# Peripheral.net
KiCad netlist of a schematic drawn in Altium Designer
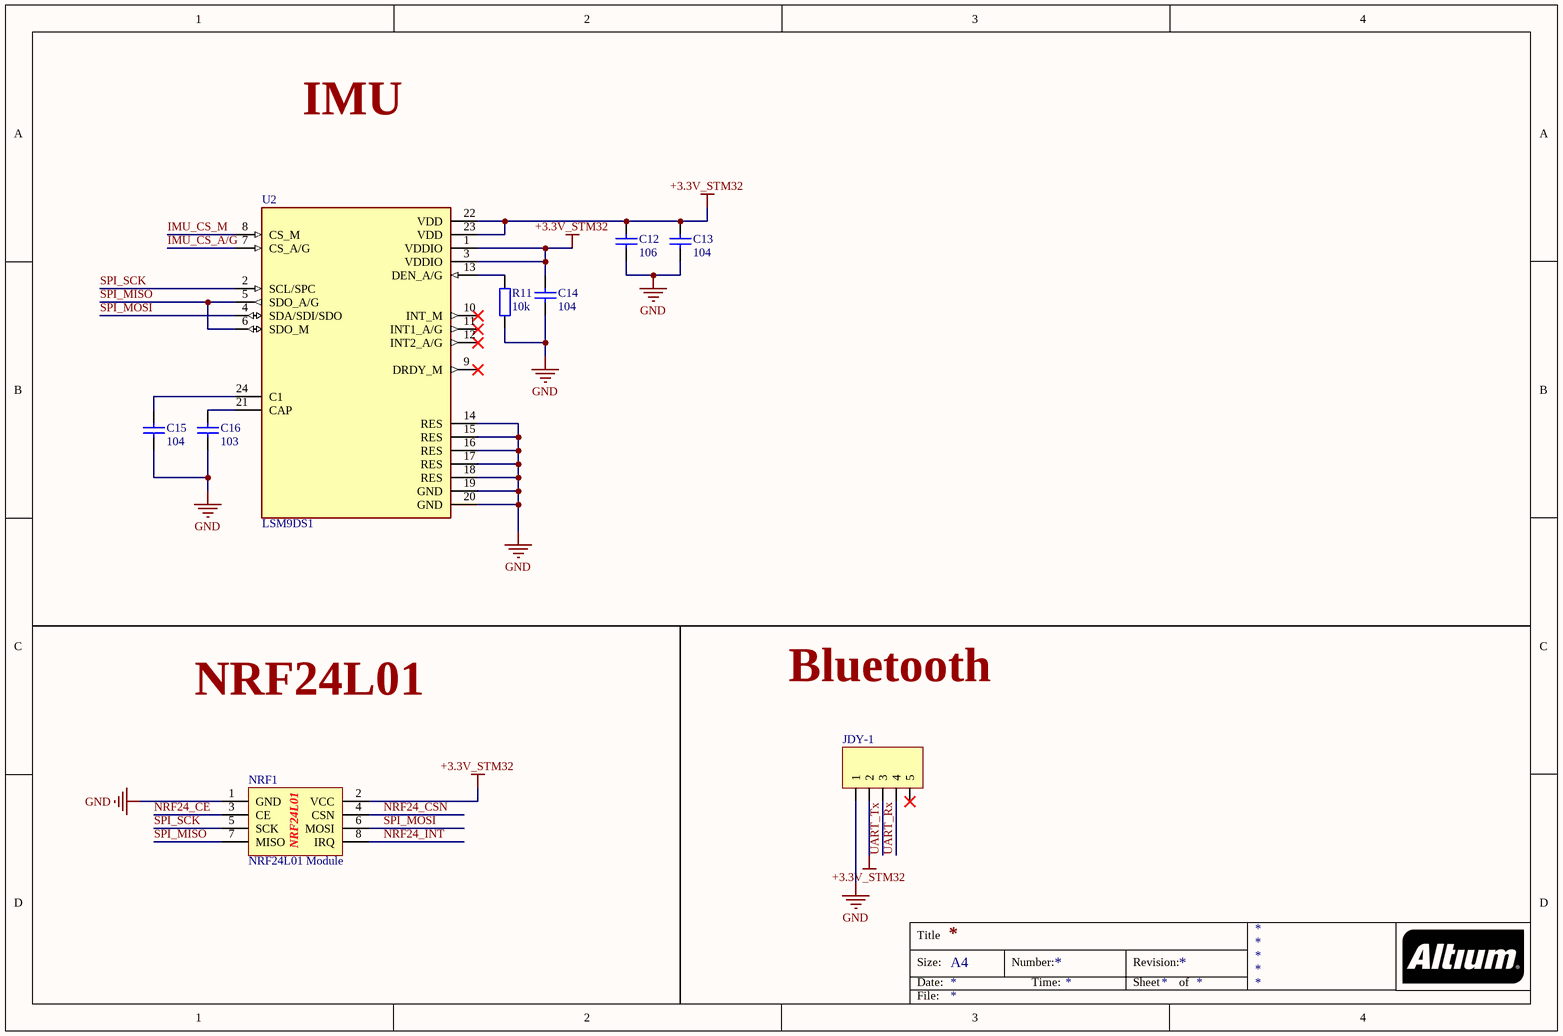
[diagram p0: Peripheral.SchDoc]

(export (version "E")
  (design (tool "Eeschema 10.0.6"))
  (components
    (comp (ref "C12")
      (value "106")
      (footprint "tu 0603")
      (description "Dán")
      (libsource (lib "Altium_Lib_by_KhueNguyenCreator") (part "Tu 0603 106 16V 20%"))
    )
    (comp (ref "C13")
      (value "104")
      (footprint "tu 0603")
      (description "Dán")
      (libsource (lib "Altium_Lib_by_KhueNguyenCreator") (part "Tu 0603 104 50V 10%"))
    )
    (comp (ref "C14")
      (value "104")
      (footprint "tu 0603")
      (description "Dán")
      (libsource (lib "Altium_Lib_by_KhueNguyenCreator") (part "Tu 0603 104 50V 10%"))
    )
    (comp (ref "C15")
      (value "104")
      (footprint "tu 0603")
      (description "Dán")
      (libsource (lib "Altium_Lib_by_KhueNguyenCreator") (part "Tu 0603 104 50V 10%"))
    )
    (comp (ref "C16")
      (value "103")
      (footprint "tu 0603")
      (description "Dán")
      (libsource (lib "Altium_Lib_by_KhueNguyenCreator") (part "Tu 0603 103 50V 10%"))
    )
    (comp (ref "JDY-1")
      (value "JP 1x5 2.54")
      (footprint "JP 1x5 CC")
      (description "Cắm")
      (libsource (lib "Altium_Lib_by_KhueNguyenCreator") (part "JP 1x5 2.54 Cai Cong"))
    )
    (comp (ref "NRF1")
      (value "NRF24L01 Module")
      (footprint "NRF24L01")
      (libsource (lib "Altium_Lib_by_KhueNguyenCreator") (part "NRF24L01 Module"))
    )
    (comp (ref "R11")
      (value "10k")
      (footprint "tro smd 0603")
      (description "Dán")
      (libsource (lib "Altium_Lib_by_KhueNguyenCreator") (part "Tro 0603 1% 10k"))
    )
    (comp (ref "U2")
      (value "LSM9DS1")
      (footprint "LSM9DS1:PQFN24P43_350X300X102L35X23N")
      (description "iNEMO inertial module: 3D accelerometer, 3D gyroscope, 3D magnetometer")
      (fields (field (name "MF") "{'manufacturer': u'STMicroelectronics'}"))
      (libsource (lib "*") (part "LSM9DS1"))
    )
  )
  (nets
    (net (code "1") (name "+3.3V_STM32") (class "Default")
      (node (ref "C12") (pin "2") (pinfunction "2_2") (pintype "passive"))
      (node (ref "C13") (pin "1") (pinfunction "1_1") (pintype "passive"))
      (node (ref "C14") (pin "1") (pinfunction "1_1") (pintype "passive"))
      (node (ref "JDY-1") (pin "2") (pinfunction "2_2") (pintype "passive"))
      (node (ref "NRF1") (pin "2") (pinfunction "VCC_2") (pintype "passive"))
      (node (ref "U2") (pin "1") (pinfunction "VDDIO_1") (pintype "power_in"))
      (node (ref "U2") (pin "22") (pinfunction "VDD_22") (pintype "power_in"))
      (node (ref "U2") (pin "23") (pinfunction "VDD_23") (pintype "power_in"))
      (node (ref "U2") (pin "3") (pinfunction "VDDIO_3") (pintype "power_in"))
    )
    (net (code "2") (name "/IMU_CS_A{slash}G") (class "Default")
      (node (ref "U2") (pin "7") (pinfunction "CS_A/G_7") (pintype "input"))
    )
    (net (code "3") (name "/IMU_CS_M") (class "Default")
      (node (ref "U2") (pin "8") (pinfunction "CS_M_8") (pintype "input"))
    )
    (net (code "4") (name "/NRF24_CE") (class "Default")
      (node (ref "NRF1") (pin "3") (pinfunction "CE_3") (pintype "passive"))
    )
    (net (code "5") (name "/NRF24_CSN") (class "Default")
      (node (ref "NRF1") (pin "4") (pinfunction "CSN_4") (pintype "passive"))
    )
    (net (code "6") (name "/NRF24_INT") (class "Default")
      (node (ref "NRF1") (pin "8") (pinfunction "IRQ_8") (pintype "passive"))
    )
    (net (code "7") (name "/SPI_MISO") (class "Default")
      (node (ref "NRF1") (pin "7") (pinfunction "MISO_7") (pintype "passive"))
      (node (ref "U2") (pin "5") (pinfunction "SDO_A/G_5") (pintype "output"))
      (node (ref "U2") (pin "6") (pinfunction "SDO_M_6") (pintype "bidirectional"))
    )
    (net (code "8") (name "/SPI_MOSI") (class "Default")
      (node (ref "NRF1") (pin "6") (pinfunction "MOSI_6") (pintype "passive"))
      (node (ref "U2") (pin "4") (pinfunction "SDA/SDI/SDO_4") (pintype "bidirectional"))
    )
    (net (code "9") (name "/SPI_SCK") (class "Default")
      (node (ref "NRF1") (pin "5") (pinfunction "SCK_5") (pintype "passive"))
      (node (ref "U2") (pin "2") (pinfunction "SCL/SPC_2") (pintype "input"))
    )
    (net (code "10") (name "/UART_Rx") (class "Default")
      (node (ref "JDY-1") (pin "4") (pinfunction "4_4") (pintype "passive"))
    )
    (net (code "11") (name "/UART_Tx") (class "Default")
      (node (ref "JDY-1") (pin "3") (pinfunction "3_3") (pintype "passive"))
    )
    (net (code "12") (name "GND") (class "Default")
      (node (ref "C12") (pin "1") (pinfunction "1_1") (pintype "passive"))
      (node (ref "C13") (pin "2") (pinfunction "2_2") (pintype "passive"))
      (node (ref "C14") (pin "2") (pinfunction "2_2") (pintype "passive"))
      (node (ref "C15") (pin "1") (pinfunction "1_1") (pintype "passive"))
      (node (ref "C16") (pin "1") (pinfunction "1_1") (pintype "passive"))
      (node (ref "JDY-1") (pin "1") (pinfunction "1_1") (pintype "passive"))
      (node (ref "NRF1") (pin "1") (pinfunction "GND_1") (pintype "passive"))
      (node (ref "R11") (pin "1") (pinfunction "1_1") (pintype "passive"))
      (node (ref "U2") (pin "14") (pinfunction "RES_14") (pintype "power_in"))
      (node (ref "U2") (pin "15") (pinfunction "RES_15") (pintype "power_in"))
      (node (ref "U2") (pin "16") (pinfunction "RES_16") (pintype "power_in"))
      (node (ref "U2") (pin "17") (pinfunction "RES_17") (pintype "power_in"))
      (node (ref "U2") (pin "18") (pinfunction "RES_18") (pintype "power_in"))
      (node (ref "U2") (pin "19") (pinfunction "GND_19") (pintype "power_in"))
      (node (ref "U2") (pin "20") (pinfunction "GND_20") (pintype "power_in"))
    )
    (net (code "13") (name "Net-(U2-C1)") (class "Default")
      (node (ref "C15") (pin "2") (pinfunction "2_2") (pintype "passive"))
      (node (ref "U2") (pin "24") (pinfunction "C1_24") (pintype "passive"))
    )
    (net (code "14") (name "Net-(U2-CAP)") (class "Default")
      (node (ref "C16") (pin "2") (pinfunction "2_2") (pintype "passive"))
      (node (ref "U2") (pin "21") (pinfunction "CAP_21") (pintype "passive"))
    )
    (net (code "15") (name "Net-(U2-DEN_A{slash}G)") (class "Default")
      (node (ref "R11") (pin "2") (pinfunction "2_2") (pintype "passive"))
      (node (ref "U2") (pin "13") (pinfunction "DEN_A/G_13") (pintype "input"))
    )
    (net (code "16") (name "unconnected-(JDY-1-Pad5)") (class "Default")
      (node (ref "JDY-1") (pin "5") (pinfunction "5_5") (pintype "passive+no_connect"))
    )
    (net (code "17") (name "unconnected-(U2-DRDY_M-Pad9)") (class "Default")
      (node (ref "U2") (pin "9") (pinfunction "DRDY_M_9") (pintype "output+no_connect"))
    )
    (net (code "18") (name "unconnected-(U2-INT1_A{slash}G-Pad11)") (class "Default")
      (node (ref "U2") (pin "11") (pinfunction "INT1_A/G_11") (pintype "output+no_connect"))
    )
    (net (code "19") (name "unconnected-(U2-INT2_A{slash}G-Pad12)") (class "Default")
      (node (ref "U2") (pin "12") (pinfunction "INT2_A/G_12") (pintype "output+no_connect"))
    )
    (net (code "20") (name "unconnected-(U2-INT_M-Pad10)") (class "Default")
      (node (ref "U2") (pin "10") (pinfunction "INT_M_10") (pintype "output+no_connect"))
    )
  )
)
